# ZippyLighthouseCircuit_v15.net
KiCad netlist of a schematic drawn in EAGLE
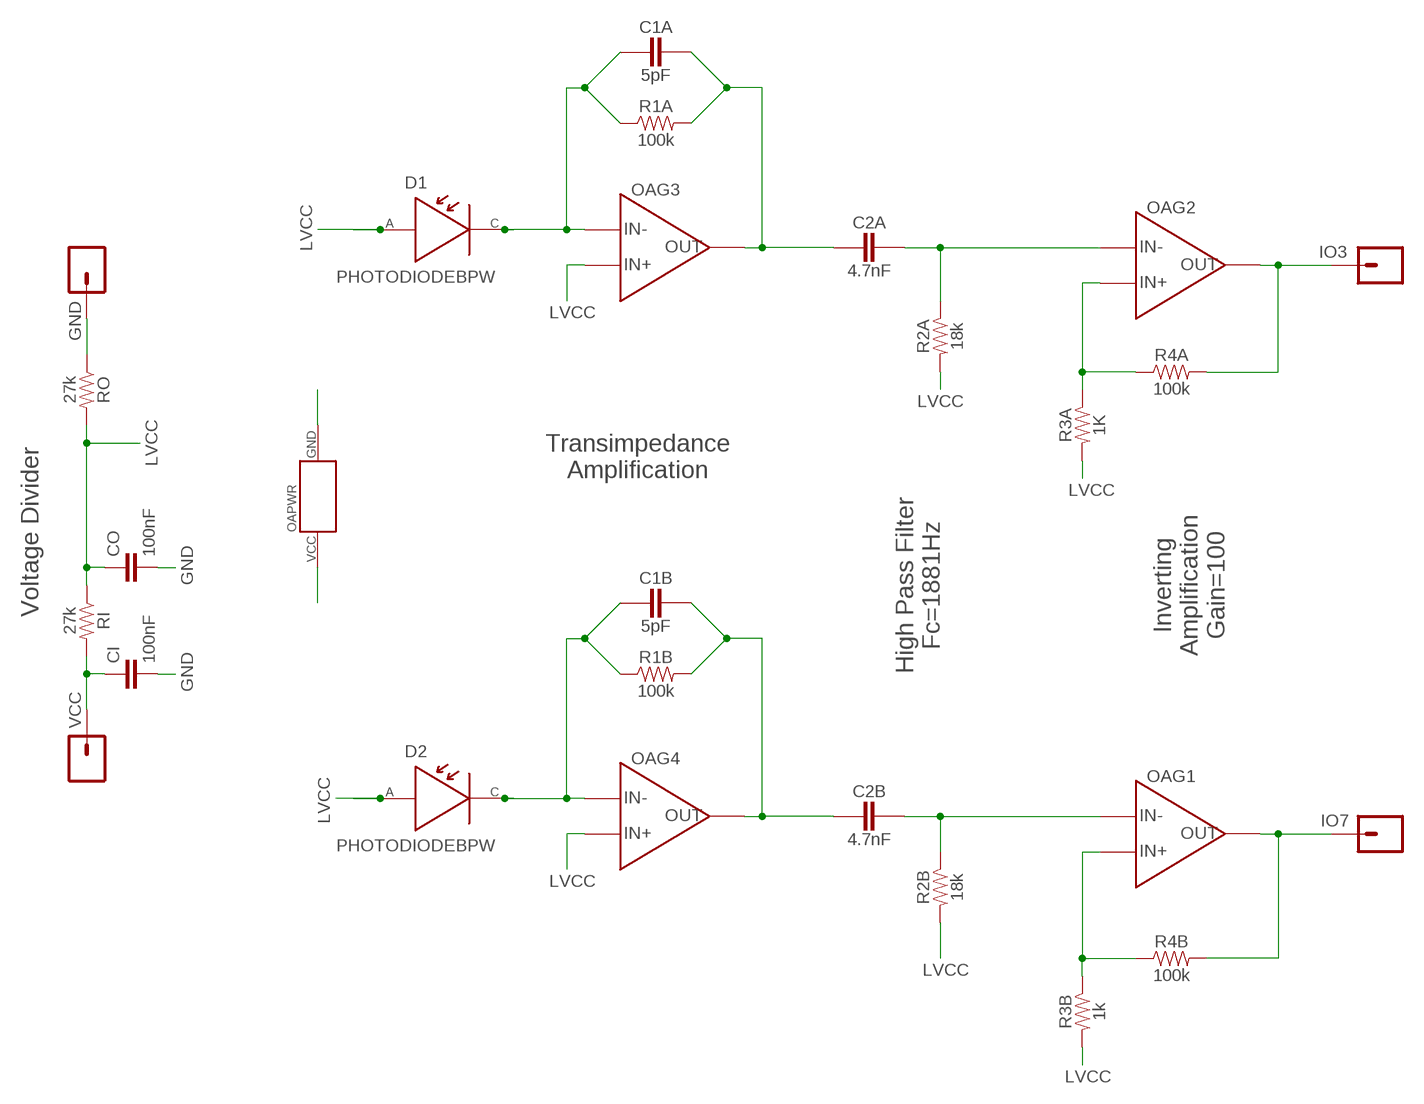
[diagram p0: schematic, sheet 1]

(export (version "E")
  (design (tool "Eeschema 10.0.6"))
  (components
    (comp (ref "C1A")
      (value "5pF")
      (footprint "eagle-import:PASSIVE-0603")
      (libsource (lib "eagle-import") (part "CAPACITOR"))
    )
    (comp (ref "C1B")
      (value "5pF")
      (footprint "eagle-import:PASSIVE-0603")
      (libsource (lib "eagle-import") (part "CAPACITOR"))
    )
    (comp (ref "C2A")
      (value "4.7nF")
      (footprint "eagle-import:PASSIVE-0603")
      (libsource (lib "eagle-import") (part "CAPACITOR"))
    )
    (comp (ref "C2B")
      (value "4.7nF")
      (footprint "eagle-import:PASSIVE-0603")
      (libsource (lib "eagle-import") (part "CAPACITOR"))
    )
    (comp (ref "CI")
      (value "100nF")
      (footprint "eagle-import:0603")
      (libsource (lib "eagle-import") (part "4.7PF-0603-50V-5%"))
    )
    (comp (ref "CO")
      (value "100nF")
      (footprint "eagle-import:0603")
      (libsource (lib "eagle-import") (part "4.7PF-0603-50V-5%"))
    )
    (comp (ref "D1")
      (value "PHOTODIODEBPW")
      (footprint "eagle-import:BPW34_BP104_SMD")
      (libsource (lib "eagle-import") (part "PHOTODIODEBPW"))
    )
    (comp (ref "D2")
      (value "PHOTODIODEBPW")
      (footprint "eagle-import:BPW34_BP104_SMD")
      (libsource (lib "eagle-import") (part "PHOTODIODEBPW"))
    )
    (comp (ref "GND")
      (value "CONN_01PTH_NO_SILK_YES_STOP")
      (footprint "eagle-import:1X01_NO_SILK")
      (libsource (lib "eagle-import") (part "CONN_01PTH_NO_SILK_YES_STOP"))
    )
    (comp (ref "IO3")
      (value "CONN_01PTH_NO_SILK_YES_STOP")
      (footprint "eagle-import:1X01_NO_SILK")
      (libsource (lib "eagle-import") (part "CONN_01PTH_NO_SILK_YES_STOP"))
    )
    (comp (ref "IO7")
      (value "CONN_01PTH_NO_SILK_YES_STOP")
      (footprint "eagle-import:1X01_NO_SILK")
      (libsource (lib "eagle-import") (part "CONN_01PTH_NO_SILK_YES_STOP"))
    )
    (comp (ref "OA")
      (value "TLV2464IDM")
      (footprint "eagle-import:D14-M")
      (libsource (lib "eagle-import") (part "TLV2464IDM"))
    )
    (comp (ref "R1A")
      (value "100k")
      (footprint "eagle-import:PASSIVE-0603")
      (libsource (lib "eagle-import") (part "RESISTOR"))
    )
    (comp (ref "R1B")
      (value "100k")
      (footprint "eagle-import:PASSIVE-0603")
      (libsource (lib "eagle-import") (part "RESISTOR"))
    )
    (comp (ref "R2A")
      (value "18k")
      (footprint "eagle-import:PASSIVE-0603")
      (libsource (lib "eagle-import") (part "RESISTOR"))
    )
    (comp (ref "R2B")
      (value "18k")
      (footprint "eagle-import:PASSIVE-0603")
      (libsource (lib "eagle-import") (part "RESISTOR"))
    )
    (comp (ref "R3A")
      (value "1K")
      (footprint "eagle-import:PASSIVE-0603")
      (libsource (lib "eagle-import") (part "RESISTOR"))
    )
    (comp (ref "R3B")
      (value "1k")
      (footprint "eagle-import:PASSIVE-0603")
      (libsource (lib "eagle-import") (part "RESISTOR"))
    )
    (comp (ref "R4A")
      (value "100k")
      (footprint "eagle-import:PASSIVE-0603")
      (libsource (lib "eagle-import") (part "RESISTOR"))
    )
    (comp (ref "R4B")
      (value "100k")
      (footprint "eagle-import:PASSIVE-0603")
      (libsource (lib "eagle-import") (part "RESISTOR"))
    )
    (comp (ref "RI")
      (value "27k")
      (footprint "eagle-import:0603")
      (libsource (lib "eagle-import") (part "100KOHM-0603-1/10W-1%"))
    )
    (comp (ref "RO")
      (value "27k")
      (footprint "eagle-import:0603")
      (libsource (lib "eagle-import") (part "100KOHM-0603-1/10W-1%"))
    )
    (comp (ref "VCC")
      (value "CONN_01PTH_NO_SILK_YES_STOP")
      (footprint "eagle-import:1X01_NO_SILK")
      (libsource (lib "eagle-import") (part "CONN_01PTH_NO_SILK_YES_STOP"))
    )
  )
  (nets
    (net (code "1") (name "/GND") (class "Default")
      (node (ref "CI") (pin "2") (pinfunction "2_2") (pintype "passive"))
      (node (ref "CO") (pin "2") (pinfunction "2_2") (pintype "passive"))
      (node (ref "GND") (pin "1") (pinfunction "1_1") (pintype "passive"))
      (node (ref "OA") (pin "11") (pinfunction "GND_11") (pintype "bidirectional"))
      (node (ref "RO") (pin "1") (pinfunction "1_1") (pintype "passive"))
    )
    (net (code "2") (name "/IO3") (class "Default")
      (node (ref "IO3") (pin "1") (pinfunction "1_1") (pintype "passive"))
      (node (ref "OA") (pin "7") (pinfunction "OUT_7") (pintype "bidirectional"))
      (node (ref "R4A") (pin "2") (pinfunction "2_2") (pintype "passive"))
    )
    (net (code "3") (name "/IO7") (class "Default")
      (node (ref "IO7") (pin "1") (pinfunction "1_1") (pintype "passive"))
      (node (ref "OA") (pin "1") (pinfunction "OUT_1") (pintype "bidirectional"))
      (node (ref "R4B") (pin "2") (pinfunction "2_2") (pintype "passive"))
    )
    (net (code "4") (name "/LVCC") (class "Default")
      (node (ref "CO") (pin "1") (pinfunction "1_1") (pintype "passive"))
      (node (ref "D1") (pin "ANODE") (pinfunction "ANODE_ANODE") (pintype "bidirectional"))
      (node (ref "D2") (pin "ANODE") (pinfunction "ANODE_ANODE") (pintype "bidirectional"))
      (node (ref "OA") (pin "10") (pinfunction "IN+_10") (pintype "bidirectional"))
      (node (ref "OA") (pin "12") (pinfunction "IN+_12") (pintype "bidirectional"))
      (node (ref "R2A") (pin "2") (pinfunction "2_2") (pintype "passive"))
      (node (ref "R2B") (pin "2") (pinfunction "2_2") (pintype "passive"))
      (node (ref "R3A") (pin "2") (pinfunction "2_2") (pintype "passive"))
      (node (ref "R3B") (pin "2") (pinfunction "2_2") (pintype "passive"))
      (node (ref "RI") (pin "1") (pinfunction "1_1") (pintype "passive"))
      (node (ref "RO") (pin "2") (pinfunction "2_2") (pintype "passive"))
    )
    (net (code "5") (name "/VCC") (class "Default")
      (node (ref "CI") (pin "1") (pinfunction "1_1") (pintype "passive"))
      (node (ref "OA") (pin "4") (pinfunction "VCC_4") (pintype "bidirectional"))
      (node (ref "RI") (pin "2") (pinfunction "2_2") (pintype "passive"))
      (node (ref "VCC") (pin "1") (pinfunction "1_1") (pintype "passive"))
    )
    (net (code "6") (name "Net-(OAA-IN+)") (class "Default")
      (node (ref "OA") (pin "3") (pinfunction "IN+_3") (pintype "bidirectional"))
      (node (ref "R3B") (pin "1") (pinfunction "1_1") (pintype "passive"))
      (node (ref "R4B") (pin "1") (pinfunction "1_1") (pintype "passive"))
    )
    (net (code "7") (name "Net-(OAA-IN-)") (class "Default")
      (node (ref "C2B") (pin "2") (pinfunction "2_2") (pintype "passive"))
      (node (ref "OA") (pin "2") (pinfunction "IN-_2") (pintype "bidirectional"))
      (node (ref "R2B") (pin "1") (pinfunction "1_1") (pintype "passive"))
    )
    (net (code "8") (name "Net-(OAB-IN+)") (class "Default")
      (node (ref "OA") (pin "5") (pinfunction "IN+_5") (pintype "bidirectional"))
      (node (ref "R3A") (pin "1") (pinfunction "1_1") (pintype "passive"))
      (node (ref "R4A") (pin "1") (pinfunction "1_1") (pintype "passive"))
    )
    (net (code "9") (name "Net-(OAB-IN-)") (class "Default")
      (node (ref "C2A") (pin "2") (pinfunction "2_2") (pintype "passive"))
      (node (ref "OA") (pin "6") (pinfunction "IN-_6") (pintype "bidirectional"))
      (node (ref "R2A") (pin "1") (pinfunction "1_1") (pintype "passive"))
    )
    (net (code "10") (name "Net-(OAC-IN-)") (class "Default")
      (node (ref "C1A") (pin "1") (pinfunction "1_1") (pintype "passive"))
      (node (ref "D1") (pin "CATHODE") (pinfunction "CATHODE_CATHODE") (pintype "bidirectional"))
      (node (ref "OA") (pin "9") (pinfunction "IN-_9") (pintype "bidirectional"))
      (node (ref "R1A") (pin "1") (pinfunction "1_1") (pintype "passive"))
    )
    (net (code "11") (name "Net-(OAC-OUT)") (class "Default")
      (node (ref "C1A") (pin "2") (pinfunction "2_2") (pintype "passive"))
      (node (ref "C2A") (pin "1") (pinfunction "1_1") (pintype "passive"))
      (node (ref "OA") (pin "8") (pinfunction "OUT_8") (pintype "bidirectional"))
      (node (ref "R1A") (pin "2") (pinfunction "2_2") (pintype "passive"))
    )
    (net (code "12") (name "Net-(OAD-IN-)") (class "Default")
      (node (ref "C1B") (pin "1") (pinfunction "1_1") (pintype "passive"))
      (node (ref "D2") (pin "CATHODE") (pinfunction "CATHODE_CATHODE") (pintype "bidirectional"))
      (node (ref "OA") (pin "13") (pinfunction "IN-_13") (pintype "bidirectional"))
      (node (ref "R1B") (pin "1") (pinfunction "1_1") (pintype "passive"))
    )
    (net (code "13") (name "Net-(OAD-OUT)") (class "Default")
      (node (ref "C1B") (pin "2") (pinfunction "2_2") (pintype "passive"))
      (node (ref "C2B") (pin "1") (pinfunction "1_1") (pintype "passive"))
      (node (ref "OA") (pin "14") (pinfunction "OUT_14") (pintype "bidirectional"))
      (node (ref "R1B") (pin "2") (pinfunction "2_2") (pintype "passive"))
    )
  )
)
